# Sheet2.net
KiCad netlist of a schematic drawn in Altium Designer
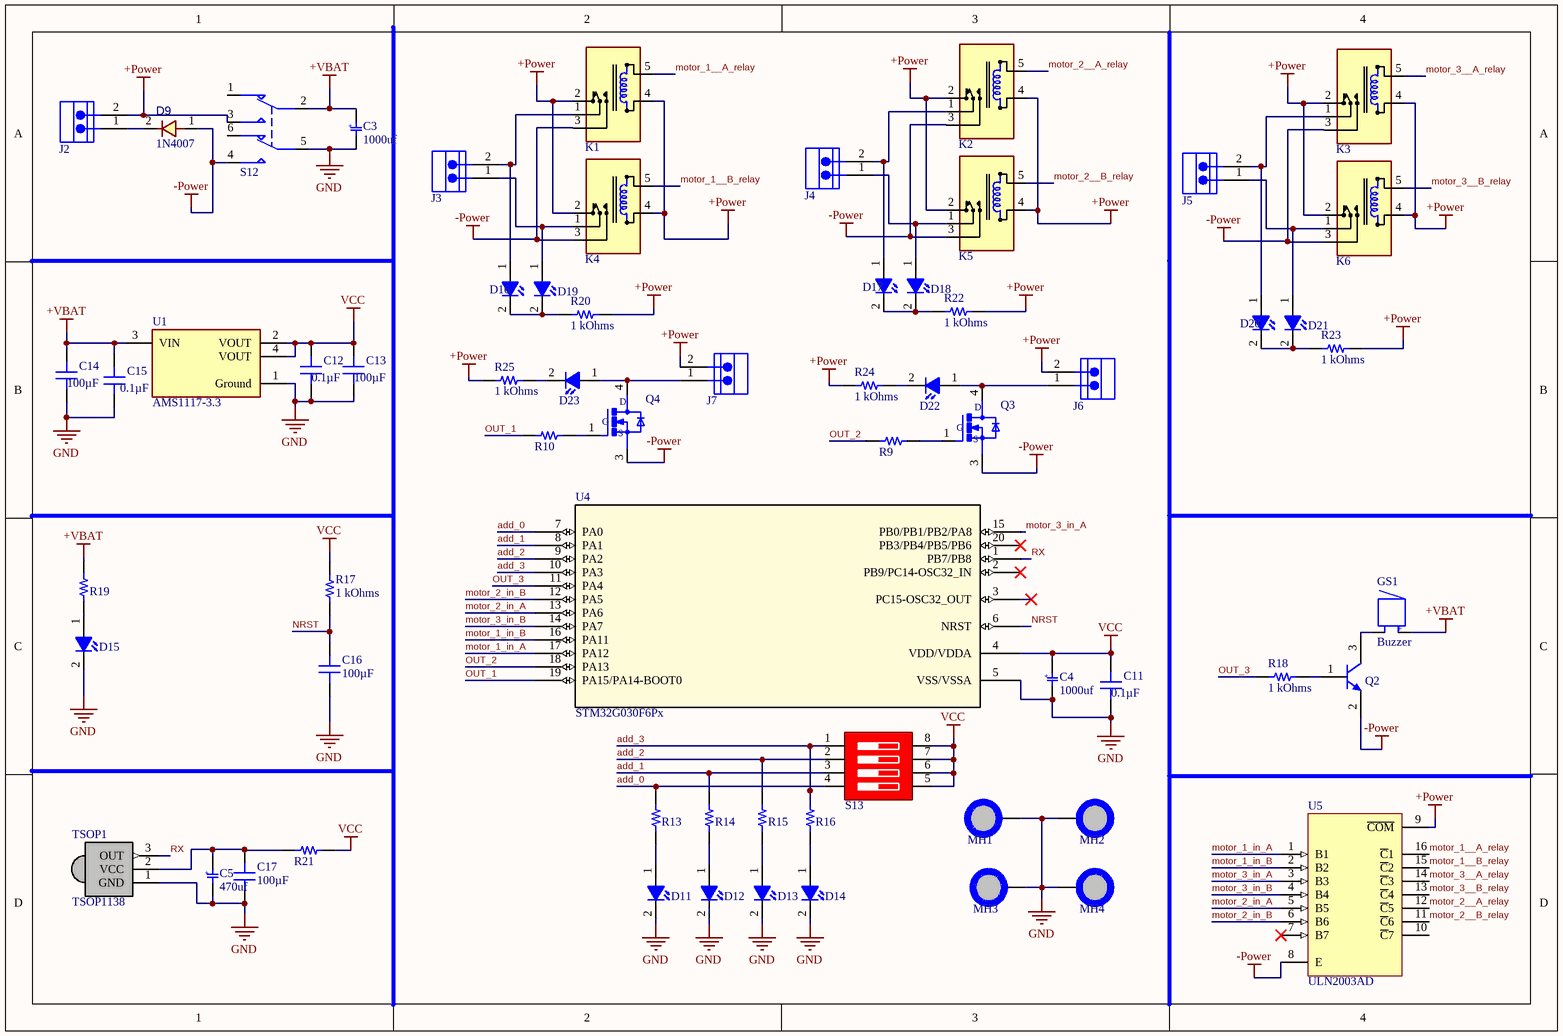
[diagram p0: Sheet2.SchDoc]

(export (version "E")
  (design (tool "Eeschema 10.0.6"))
  (components
    (comp (ref "C3")
      (value "1000uf")
      (footprint "Cap_3_(3.5mm)")
      (description "Capacitor Electrical THD")
      (libsource (lib "Schlib1") (part "Capacitor Electrical THD"))
    )
    (comp (ref "C4")
      (value "1000uf")
      (footprint "Cap_3_(3.5mm)")
      (description "Capacitor Electrical THD")
      (libsource (lib "Schlib1") (part "Capacitor Electrical THD"))
    )
    (comp (ref "C5")
      (value "470uf")
      (footprint "Cap_3_(3.5mm)")
      (description "Capacitor Electrical THD")
      (libsource (lib "Schlib1") (part "Capacitor Electrical THD"))
    )
    (comp (ref "C11")
      (value "0.1µF")
      (footprint "CAP 0805_2012")
      (description "CAP CER 0805 10% X8R 50V 100NF")
      (fields (field (name "PART NUMBER") "AC0805KKX8R9BB104") (field (name "MANUFACTURER") "Yageo"))
      (libsource (lib "Database_Libs1") (part "Capacitor"))
    )
    (comp (ref "C12")
      (value "0.1µF")
      (footprint "CAP 0805_2012")
      (description "CAP CER 0805 10% X8R 50V 100NF")
      (fields (field (name "PART NUMBER") "AC0805KKX8R9BB104") (field (name "MANUFACTURER") "Yageo"))
      (libsource (lib "Database_Libs1") (part "Capacitor"))
    )
    (comp (ref "C13")
      (value "100µF")
      (footprint "CAP 0805_2012")
      (description "CAP CER 100UF 6.3V X5R 0805")
      (fields
        (field (name "PART NUMBER") "GRM21BR60J107ME15L")
        (field (name "MANUFACTURER") "Murata Electronics")
      )
      (libsource (lib "Database_Libs1") (part "Capacitor"))
    )
    (comp (ref "C14")
      (value "100µF")
      (footprint "CAP 0805_2012")
      (description "CAP CER 100UF 6.3V X5R 0805")
      (fields
        (field (name "PART NUMBER") "GRM21BR60J107ME15L")
        (field (name "MANUFACTURER") "Murata Electronics")
      )
      (libsource (lib "Database_Libs1") (part "Capacitor"))
    )
    (comp (ref "C15")
      (value "0.1µF")
      (footprint "CAP 0805_2012")
      (description "CAP CER 0805 10% X8R 50V 100NF")
      (fields (field (name "PART NUMBER") "AC0805KKX8R9BB104") (field (name "MANUFACTURER") "Yageo"))
      (libsource (lib "Database_Libs1") (part "Capacitor"))
    )
    (comp (ref "C16")
      (value "100µF")
      (footprint "CAP 0805_2012")
      (description "CAP CER 100UF 6.3V X5R 0805")
      (fields
        (field (name "PART NUMBER") "GRM21BR60J107ME15L")
        (field (name "MANUFACTURER") "Murata Electronics")
      )
      (libsource (lib "Database_Libs1") (part "Capacitor"))
    )
    (comp (ref "C17")
      (value "100µF")
      (footprint "CAP 0805_2012")
      (description "CAP CER 100UF 6.3V X5R 0805")
      (fields
        (field (name "PART NUMBER") "GRM21BR60J107ME15L")
        (field (name "MANUFACTURER") "Murata Electronics")
      )
      (libsource (lib "Database_Libs1") (part "Capacitor"))
    )
    (comp (ref "D9")
      (value "1N4007")
      (footprint "D_SMA")
      (description "DIODE, GENERAL PURPOSE, 1000V/1A")
      (fields (field (name "Comment") "1N4007 SMD M7"))
      (libsource (lib "Schlib1") (part "1N4007 SMD M7"))
    )
    (comp (ref "D11")
      (value "LED THD 3mm")
      (footprint "LED THD 3mm (White)")
      (libsource (lib "Schlib1") (part "LED THD 3mm"))
    )
    (comp (ref "D12")
      (value "LED THD 3mm")
      (footprint "LED THD 3mm (White)")
      (libsource (lib "Schlib1") (part "LED THD 3mm"))
    )
    (comp (ref "D13")
      (value "LED THD 3mm")
      (footprint "LED THD 3mm (White)")
      (libsource (lib "Schlib1") (part "LED THD 3mm"))
    )
    (comp (ref "D14")
      (value "LED THD 3mm")
      (footprint "LED THD 3mm (White)")
      (libsource (lib "Schlib1") (part "LED THD 3mm"))
    )
    (comp (ref "D15")
      (value "LED THD 3mm")
      (footprint "LED THD 3mm (White)")
      (libsource (lib "Schlib1") (part "LED THD 3mm"))
    )
    (comp (ref "D16")
      (value "LED THD 3mm")
      (footprint "LED THD 3mm (White)")
      (libsource (lib "Schlib1") (part "LED THD 3mm"))
    )
    (comp (ref "D17")
      (value "LED THD 3mm")
      (footprint "LED THD 3mm (White)")
      (libsource (lib "Schlib1") (part "LED THD 3mm"))
    )
    (comp (ref "D18")
      (value "LED THD 3mm")
      (footprint "LED THD 3mm (White)")
      (libsource (lib "Schlib1") (part "LED THD 3mm"))
    )
    (comp (ref "D19")
      (value "LED THD 3mm")
      (footprint "LED THD 3mm (White)")
      (libsource (lib "Schlib1") (part "LED THD 3mm"))
    )
    (comp (ref "D20")
      (value "LED THD 3mm")
      (footprint "LED THD 3mm (White)")
      (libsource (lib "Schlib1") (part "LED THD 3mm"))
    )
    (comp (ref "D21")
      (value "LED THD 3mm")
      (footprint "LED THD 3mm (White)")
      (libsource (lib "Schlib1") (part "LED THD 3mm"))
    )
    (comp (ref "D22")
      (value "LED THD 3mm")
      (footprint "LED THD 3mm (White)")
      (libsource (lib "Schlib1") (part "LED THD 3mm"))
    )
    (comp (ref "D23")
      (value "LED THD 3mm")
      (footprint "LED THD 3mm (White)")
      (libsource (lib "Schlib1") (part "LED THD 3mm"))
    )
    (comp (ref "GS1")
      (value "Buzzer")
      (footprint "BZ_SJ")
      (description "Magnetic Transducer Buzzer")
      (fields (field (name "DESIGNER") "Eng. Saeid Jorablo") (field (name "PUBLISHER") "SJ Unlimited"))
      (libsource (lib "Schlib1") (part "Buzzer"))
    )
    (comp (ref "J2")
      (value "Socket Blue 2")
      (footprint "Socket Blue 2")
      (libsource (lib "Schlib1") (part "Socket Blue 2"))
    )
    (comp (ref "J3")
      (value "Socket Blue 2")
      (footprint "Socket Blue 2")
      (libsource (lib "Schlib1") (part "Socket Blue 2"))
    )
    (comp (ref "J4")
      (value "Socket Blue 2")
      (footprint "Socket Blue 2")
      (libsource (lib "Schlib1") (part "Socket Blue 2"))
    )
    (comp (ref "J5")
      (value "Socket Blue 2")
      (footprint "Socket Blue 2")
      (libsource (lib "Schlib1") (part "Socket Blue 2"))
    )
    (comp (ref "J6")
      (value "Socket Blue 2")
      (footprint "Socket Blue 2")
      (libsource (lib "Schlib1") (part "Socket Blue 2"))
    )
    (comp (ref "J7")
      (value "Socket Blue 2")
      (footprint "Socket Blue 2")
      (libsource (lib "Schlib1") (part "Socket Blue 2"))
    )
    (comp (ref "K1")
      (value "RELAY SPST 5 Pin Millon")
      (footprint "REL_SPDT_5_2216")
      (description "Relay")
      (libsource (lib "Schlib1") (part "RELAY SPST 5 Pin Millon"))
    )
    (comp (ref "K2")
      (value "RELAY SPST 5 Pin Millon")
      (footprint "REL_SPDT_5_2216")
      (description "Relay")
      (libsource (lib "Schlib1") (part "RELAY SPST 5 Pin Millon"))
    )
    (comp (ref "K3")
      (value "RELAY SPST 5 Pin Millon")
      (footprint "REL_SPDT_5_2216")
      (description "Relay")
      (libsource (lib "Schlib1") (part "RELAY SPST 5 Pin Millon"))
    )
    (comp (ref "K4")
      (value "RELAY SPST 5 Pin Millon")
      (footprint "REL_SPDT_5_2216")
      (description "Relay")
      (libsource (lib "Schlib1") (part "RELAY SPST 5 Pin Millon"))
    )
    (comp (ref "K5")
      (value "RELAY SPST 5 Pin Millon")
      (footprint "REL_SPDT_5_2216")
      (description "Relay")
      (libsource (lib "Schlib1") (part "RELAY SPST 5 Pin Millon"))
    )
    (comp (ref "K6")
      (value "RELAY SPST 5 Pin Millon")
      (footprint "REL_SPDT_5_2216")
      (description "Relay")
      (libsource (lib "Schlib1") (part "RELAY SPST 5 Pin Millon"))
    )
    (comp (ref "MH1")
      (value "MH_7.4mmC_3.2mmD")
      (footprint "MH_7.4mmC_3.2mmD")
      (description "MH_7.4MM Diameter,3.2mm Drill")
      (libsource (lib "Schlib1") (part "MH_7.4mmC_3.2mmD"))
    )
    (comp (ref "MH2")
      (value "MH_7.4mmC_3.2mmD")
      (footprint "MH_7.4mmC_3.2mmD")
      (description "MH_7.4MM Diameter,3.2mm Drill")
      (libsource (lib "Schlib1") (part "MH_7.4mmC_3.2mmD"))
    )
    (comp (ref "MH3")
      (value "MH_7.4mmC_3.2mmD")
      (footprint "MH_7.4mmC_3.2mmD")
      (description "MH_7.4MM Diameter,3.2mm Drill")
      (libsource (lib "Schlib1") (part "MH_7.4mmC_3.2mmD"))
    )
    (comp (ref "MH4")
      (value "MH_7.4mmC_3.2mmD")
      (footprint "MH_7.4mmC_3.2mmD")
      (description "MH_7.4MM Diameter,3.2mm Drill")
      (libsource (lib "Schlib1") (part "MH_7.4mmC_3.2mmD"))
    )
    (comp (ref "Q2")
      (value "MMBT2222A-7-F")
      (footprint "DIODES SOT-23-3")
      (description "TRANS NPN 40V 0.6A SMD SOT23-3")
      (fields (field (name "MANUFACTURER") "Diodes Incorporated"))
      (libsource (lib "Database_Libs1") (part "DIODES INC NPN SOT-23-3"))
    )
    (comp (ref "Q3")
      (value "PHD45N03LTA")
      (footprint "PcbLib1:TO228P1000X238-3N")
      (description "Bipolar Transistors - BJT")
      (fields (field (name "MF") "NXP USA"))
      (libsource (lib "Schlib1") (part "PHD45N03LTA"))
    )
    (comp (ref "Q4")
      (value "PHD45N03LTA")
      (footprint "PcbLib1:TO228P1000X238-3N")
      (description "Bipolar Transistors - BJT")
      (fields (field (name "MF") "NXP USA"))
      (libsource (lib "Schlib1") (part "PHD45N03LTA"))
    )
    (comp (ref "R9")
      (value "100 Ohms")
      (footprint "RES 0805_2012")
      (description "RES SMD 100 OHM 1% 0.4W 0805")
      (fields (field (name "PART NUMBER") "RCS0805100RFKEA") (field (name "MANUFACTURER") "Vishay Dale"))
      (libsource (lib "Database_Libs1") (part "Resistor"))
    )
    (comp (ref "R10")
      (value "100 Ohms")
      (footprint "RES 0805_2012")
      (description "RES SMD 100 OHM 1% 0.4W 0805")
      (fields (field (name "PART NUMBER") "RCS0805100RFKEA") (field (name "MANUFACTURER") "Vishay Dale"))
      (libsource (lib "Database_Libs1") (part "Resistor"))
    )
    (comp (ref "R13")
      (value "50 mOhms")
      (footprint "RES 0805_2012")
      (description "RES 0.05 OHM 1% 1/4W 0805")
      (fields (field (name "PART NUMBER") "CRM0805-FW-R050ELF") (field (name "MANUFACTURER") "Bourns Inc."))
      (libsource (lib "Database_Libs1") (part "Resistor"))
    )
    (comp (ref "R14")
      (value "50 mOhms")
      (footprint "RES 0805_2012")
      (description "RES 0.05 OHM 1% 1/4W 0805")
      (fields (field (name "PART NUMBER") "CRM0805-FW-R050ELF") (field (name "MANUFACTURER") "Bourns Inc."))
      (libsource (lib "Database_Libs1") (part "Resistor"))
    )
    (comp (ref "R15")
      (value "50 mOhms")
      (footprint "RES 0805_2012")
      (description "RES 0.05 OHM 1% 1/4W 0805")
      (fields (field (name "PART NUMBER") "CRM0805-FW-R050ELF") (field (name "MANUFACTURER") "Bourns Inc."))
      (libsource (lib "Database_Libs1") (part "Resistor"))
    )
    (comp (ref "R16")
      (value "50 mOhms")
      (footprint "RES 0805_2012")
      (description "RES 0.05 OHM 1% 1/4W 0805")
      (fields (field (name "PART NUMBER") "CRM0805-FW-R050ELF") (field (name "MANUFACTURER") "Bourns Inc."))
      (libsource (lib "Database_Libs1") (part "Resistor"))
    )
    (comp (ref "R17")
      (value "1 kOhms")
      (footprint "RES 0805_2012")
      (description "RES 1K OHM 1% 1/4W 0805")
      (fields
        (field (name "PART NUMBER") "RNCP0805FTD1K00")
        (field (name "MANUFACTURER") "Stackpole Electronics Inc")
      )
      (libsource (lib "Database_Libs1") (part "Resistor"))
    )
    (comp (ref "R18")
      (value "1 kOhms")
      (footprint "RES 0805_2012")
      (description "RES 1K OHM 1% 1/4W 0805")
      (fields
        (field (name "PART NUMBER") "RNCP0805FTD1K00")
        (field (name "MANUFACTURER") "Stackpole Electronics Inc")
      )
      (libsource (lib "Database_Libs1") (part "Resistor"))
    )
    (comp (ref "R19")
      (value "150 Ohms")
      (footprint "RES 0805_2012")
      (description "CRGP 0805 150R 1%")
      (fields
        (field (name "PART NUMBER") "CRGP0805F150R")
        (field (name "MANUFACTURER") "TE Connectivity Passive Product")
      )
      (libsource (lib "Database_Libs1") (part "Resistor"))
    )
    (comp (ref "R20")
      (value "1 kOhms")
      (footprint "RES 0805_2012")
      (description "RES 1K OHM 1% 1/4W 0805")
      (fields
        (field (name "PART NUMBER") "RNCP0805FTD1K00")
        (field (name "MANUFACTURER") "Stackpole Electronics Inc")
      )
      (libsource (lib "Database_Libs1") (part "Resistor"))
    )
    (comp (ref "R21")
      (value "100 Ohms")
      (footprint "RES 0805_2012")
      (description "CRGP 0805 100R 1%")
      (fields
        (field (name "PART NUMBER") "CRGP0805F100R")
        (field (name "MANUFACTURER") "TE Connectivity Passive Product")
      )
      (libsource (lib "Database_Libs1") (part "Resistor"))
    )
    (comp (ref "R22")
      (value "1 kOhms")
      (footprint "RES 0805_2012")
      (description "RES 1K OHM 1% 1/4W 0805")
      (fields
        (field (name "PART NUMBER") "RNCP0805FTD1K00")
        (field (name "MANUFACTURER") "Stackpole Electronics Inc")
      )
      (libsource (lib "Database_Libs1") (part "Resistor"))
    )
    (comp (ref "R23")
      (value "1 kOhms")
      (footprint "RES 0805_2012")
      (description "RES 1K OHM 1% 1/4W 0805")
      (fields
        (field (name "PART NUMBER") "RNCP0805FTD1K00")
        (field (name "MANUFACTURER") "Stackpole Electronics Inc")
      )
      (libsource (lib "Database_Libs1") (part "Resistor"))
    )
    (comp (ref "R24")
      (value "1 kOhms")
      (footprint "RES 0805_2012")
      (description "RES 1K OHM 1% 1/4W 0805")
      (fields
        (field (name "PART NUMBER") "RNCP0805FTD1K00")
        (field (name "MANUFACTURER") "Stackpole Electronics Inc")
      )
      (libsource (lib "Database_Libs1") (part "Resistor"))
    )
    (comp (ref "R25")
      (value "1 kOhms")
      (footprint "RES 0805_2012")
      (description "RES 1K OHM 1% 1/4W 0805")
      (fields
        (field (name "PART NUMBER") "RNCP0805FTD1K00")
        (field (name "MANUFACTURER") "Stackpole Electronics Inc")
      )
      (libsource (lib "Database_Libs1") (part "Resistor"))
    )
    (comp (ref "S12")
      (value "Double Switch")
      (footprint "SWPUST_DPDT_S2")
      (description "DPDT Switch")
      (libsource (lib "Schlib1") (part "SW DPDT"))
    )
    (comp (ref "S13")
      (value "DIP Switch 4")
      (footprint "dip switch 4  Blue THD")
      (description "4 BIT DIP Switch")
      (libsource (lib "Schlib1") (part "DIP Switch 4"))
    )
    (comp (ref "TSOP1")
      (value "TSOP1138")
      (footprint "TSOP11XX & 13XX")
      (description "IR Receiver Modules for Remote Control Systems")
      (libsource (lib "Schlib1") (part "TSOP1138"))
    )
    (comp (ref "U1")
      (value "AMS1117-3.3")
      (footprint "SOT223-4N")
      (description "LDO Voltage Regulators 1A, 3.3V")
      (fields
        (field (name "OCTOPART") "https://octopart.com/ams1117-3.3-advanced+monolithic+systems-25899300")
        (field (name "MANUFACTURER") "Advanced Monolithic Systems")
      )
      (libsource (lib "Schlib1") (part "CMP-209535-000001-1"))
    )
    (comp (ref "U4")
      (value "STM32G030F6Px")
      (footprint "TSSOP20")
      (fields
        (field (name "MANUFACTURER_PART_NUMBER") "stm32g0_tssop20_t1")
        (field (name "COPYRIGHT") "Copyright (C) 2018 Accelerated Designs. All rights reserved")
      )
      (libsource (lib "ST Microelectronics STM32 G0") (part "STM32G030F6Px"))
    )
    (comp (ref "U5")
      (value "ULN2003AD")
      (footprint "SOIC16")
      (description "Darlington Transistor Array")
      (fields (field (name "PUBLISHER") "Altium Limited"))
      (libsource (lib "Schlib1") (part "ULN2003AD"))
    )
  )
  (nets
    (net (code "1") (name "+Power") (class "Default")
      (node (ref "J2") (pin "2") (pinfunction "2_2") (pintype "passive"))
      (node (ref "J6") (pin "2") (pinfunction "2_2") (pintype "passive"))
      (node (ref "J7") (pin "2") (pinfunction "2_2") (pintype "passive"))
      (node (ref "K1") (pin "2") (pinfunction "NC_2") (pintype "passive"))
      (node (ref "K1") (pin "4") (pinfunction "T1_4") (pintype "passive"))
      (node (ref "K2") (pin "2") (pinfunction "NC_2") (pintype "passive"))
      (node (ref "K2") (pin "4") (pinfunction "T1_4") (pintype "passive"))
      (node (ref "K3") (pin "2") (pinfunction "NC_2") (pintype "passive"))
      (node (ref "K3") (pin "4") (pinfunction "T1_4") (pintype "passive"))
      (node (ref "K4") (pin "2") (pinfunction "NC_2") (pintype "passive"))
      (node (ref "K4") (pin "4") (pinfunction "T1_4") (pintype "passive"))
      (node (ref "K5") (pin "2") (pinfunction "NC_2") (pintype "passive"))
      (node (ref "K5") (pin "4") (pinfunction "T1_4") (pintype "passive"))
      (node (ref "K6") (pin "2") (pinfunction "NC_2") (pintype "passive"))
      (node (ref "K6") (pin "4") (pinfunction "T1_4") (pintype "passive"))
      (node (ref "R20") (pin "2") (pinfunction "2_2") (pintype "passive"))
      (node (ref "R22") (pin "2") (pinfunction "2_2") (pintype "passive"))
      (node (ref "R23") (pin "2") (pinfunction "2_2") (pintype "passive"))
      (node (ref "R24") (pin "1") (pinfunction "1_1") (pintype "passive"))
      (node (ref "R25") (pin "1") (pinfunction "1_1") (pintype "passive"))
      (node (ref "S12") (pin "3") (pinfunction "3_3") (pintype "passive"))
      (node (ref "U5") (pin "9") (pinfunction "~{COM}_9") (pintype "passive"))
    )
    (net (code "2") (name "+VBAT") (class "Default")
      (node (ref "C14") (pin "2") (pinfunction "2_2") (pintype "passive"))
      (node (ref "C15") (pin "2") (pinfunction "2_2") (pintype "passive"))
      (node (ref "C3") (pin "1") (pinfunction "1_1") (pintype "passive"))
      (node (ref "GS1") (pin "1") (pinfunction "+_1") (pintype "passive"))
      (node (ref "R19") (pin "2") (pinfunction "2_2") (pintype "passive"))
      (node (ref "S12") (pin "2") (pinfunction "2_2") (pintype "passive"))
      (node (ref "U1") (pin "3") (pinfunction "VIN_3") (pintype "power_in"))
    )
    (net (code "3") (name "-Power") (class "Default")
      (node (ref "D9") (pin "1") (pinfunction "1_1") (pintype "passive"))
      (node (ref "K1") (pin "3") (pinfunction "NO_3") (pintype "passive"))
      (node (ref "K2") (pin "3") (pinfunction "NO_3") (pintype "passive"))
      (node (ref "K3") (pin "3") (pinfunction "NO_3") (pintype "passive"))
      (node (ref "K4") (pin "3") (pinfunction "NO_3") (pintype "passive"))
      (node (ref "K5") (pin "3") (pinfunction "NO_3") (pintype "passive"))
      (node (ref "K6") (pin "3") (pinfunction "NO_3") (pintype "passive"))
      (node (ref "Q2") (pin "2") (pinfunction "E_2") (pintype "passive"))
      (node (ref "Q3") (pin "3") (pinfunction "S_3") (pintype "passive"))
      (node (ref "Q4") (pin "3") (pinfunction "S_3") (pintype "passive"))
      (node (ref "S12") (pin "4") (pinfunction "4_4") (pintype "passive"))
      (node (ref "U5") (pin "8") (pinfunction "E_8") (pintype "power_in"))
    )
    (net (code "4") (name "/NRST") (class "Default")
      (node (ref "C16") (pin "2") (pinfunction "2_2") (pintype "passive"))
      (node (ref "R17") (pin "2") (pinfunction "2_2") (pintype "passive"))
      (node (ref "U4") (pin "6") (pinfunction "NRST_6") (pintype "bidirectional"))
    )
    (net (code "5") (name "/OUT_1") (class "Default")
      (node (ref "R10") (pin "1") (pinfunction "1_1") (pintype "passive"))
      (node (ref "U4") (pin "19") (pinfunction "PA15/PA14-BOOT0_19") (pintype "bidirectional"))
    )
    (net (code "6") (name "/OUT_2") (class "Default")
      (node (ref "R9") (pin "1") (pinfunction "1_1") (pintype "passive"))
      (node (ref "U4") (pin "18") (pinfunction "PA13_18") (pintype "bidirectional"))
    )
    (net (code "7") (name "/OUT_3") (class "Default")
      (node (ref "R18") (pin "1") (pinfunction "1_1") (pintype "passive"))
      (node (ref "U4") (pin "11") (pinfunction "PA4_11") (pintype "bidirectional"))
    )
    (net (code "8") (name "/RX") (class "Default")
      (node (ref "TSOP1") (pin "3") (pinfunction "OUT_3") (pintype "output"))
      (node (ref "U4") (pin "1") (pinfunction "PB7/PB8_1") (pintype "bidirectional"))
    )
    (net (code "9") (name "/add_0") (class "Default")
      (node (ref "R13") (pin "2") (pinfunction "2_2") (pintype "passive"))
      (node (ref "S13") (pin "4") (pinfunction "4_4") (pintype "passive"))
      (node (ref "U4") (pin "7") (pinfunction "PA0_7") (pintype "bidirectional"))
    )
    (net (code "10") (name "/add_1") (class "Default")
      (node (ref "R14") (pin "2") (pinfunction "2_2") (pintype "passive"))
      (node (ref "S13") (pin "3") (pinfunction "3_3") (pintype "passive"))
      (node (ref "U4") (pin "8") (pinfunction "PA1_8") (pintype "bidirectional"))
    )
    (net (code "11") (name "/add_2") (class "Default")
      (node (ref "R15") (pin "2") (pinfunction "2_2") (pintype "passive"))
      (node (ref "S13") (pin "2") (pinfunction "2_2") (pintype "passive"))
      (node (ref "U4") (pin "9") (pinfunction "PA2_9") (pintype "bidirectional"))
    )
    (net (code "12") (name "/add_3") (class "Default")
      (node (ref "R16") (pin "2") (pinfunction "2_2") (pintype "passive"))
      (node (ref "S13") (pin "1") (pinfunction "1_1") (pintype "passive"))
      (node (ref "U4") (pin "10") (pinfunction "PA3_10") (pintype "bidirectional"))
    )
    (net (code "13") (name "/motor_1__A_relay") (class "Default")
      (node (ref "K1") (pin "5") (pinfunction "T2_5") (pintype "passive"))
      (node (ref "U5") (pin "16") (pinfunction "~{C}1_16") (pintype "open_collector"))
    )
    (net (code "14") (name "/motor_1__B_relay") (class "Default")
      (node (ref "K4") (pin "5") (pinfunction "T2_5") (pintype "passive"))
      (node (ref "U5") (pin "15") (pinfunction "~{C}2_15") (pintype "open_collector"))
    )
    (net (code "15") (name "/motor_1_in_A") (class "Default")
      (node (ref "U4") (pin "17") (pinfunction "PA12_17") (pintype "bidirectional"))
      (node (ref "U5") (pin "1") (pinfunction "B1_1") (pintype "input"))
    )
    (net (code "16") (name "/motor_1_in_B") (class "Default")
      (node (ref "U4") (pin "16") (pinfunction "PA11_16") (pintype "bidirectional"))
      (node (ref "U5") (pin "2") (pinfunction "B2_2") (pintype "input"))
    )
    (net (code "17") (name "/motor_2__A_relay") (class "Default")
      (node (ref "K2") (pin "5") (pinfunction "T2_5") (pintype "passive"))
      (node (ref "U5") (pin "12") (pinfunction "~{C}5_12") (pintype "open_collector"))
    )
    (net (code "18") (name "/motor_2__B_relay") (class "Default")
      (node (ref "K5") (pin "5") (pinfunction "T2_5") (pintype "passive"))
      (node (ref "U5") (pin "11") (pinfunction "~{C}6_11") (pintype "open_collector"))
    )
    (net (code "19") (name "/motor_2_in_A") (class "Default")
      (node (ref "U4") (pin "13") (pinfunction "PA6_13") (pintype "bidirectional"))
      (node (ref "U5") (pin "5") (pinfunction "B5_5") (pintype "input"))
    )
    (net (code "20") (name "/motor_2_in_B") (class "Default")
      (node (ref "U4") (pin "12") (pinfunction "PA5_12") (pintype "bidirectional"))
      (node (ref "U5") (pin "6") (pinfunction "B6_6") (pintype "input"))
    )
    (net (code "21") (name "/motor_3__A_relay") (class "Default")
      (node (ref "K3") (pin "5") (pinfunction "T2_5") (pintype "passive"))
      (node (ref "U5") (pin "14") (pinfunction "~{C}3_14") (pintype "open_collector"))
    )
    (net (code "22") (name "/motor_3__B_relay") (class "Default")
      (node (ref "K6") (pin "5") (pinfunction "T2_5") (pintype "passive"))
      (node (ref "U5") (pin "13") (pinfunction "~{C}4_13") (pintype "open_collector"))
    )
    (net (code "23") (name "/motor_3_in_A") (class "Default")
      (node (ref "U4") (pin "15") (pinfunction "PB0/PB1/PB2/PA8_15") (pintype "bidirectional"))
      (node (ref "U5") (pin "3") (pinfunction "B3_3") (pintype "input"))
    )
    (net (code "24") (name "/motor_3_in_B") (class "Default")
      (node (ref "U4") (pin "14") (pinfunction "PA7_14") (pintype "bidirectional"))
      (node (ref "U5") (pin "4") (pinfunction "B4_4") (pintype "input"))
    )
    (net (code "25") (name "GND") (class "Default")
      (node (ref "C11") (pin "1") (pinfunction "1_1") (pintype "passive"))
      (node (ref "C12") (pin "1") (pinfunction "1_1") (pintype "passive"))
      (node (ref "C13") (pin "1") (pinfunction "1_1") (pintype "passive"))
      (node (ref "C14") (pin "1") (pinfunction "1_1") (pintype "passive"))
      (node (ref "C15") (pin "1") (pinfunction "1_1") (pintype "passive"))
      (node (ref "C16") (pin "1") (pinfunction "1_1") (pintype "passive"))
      (node (ref "C17") (pin "1") (pinfunction "1_1") (pintype "passive"))
      (node (ref "C3") (pin "2") (pinfunction "2_2") (pintype "passive"))
      (node (ref "C4") (pin "2") (pinfunction "2_2") (pintype "passive"))
      (node (ref "C5") (pin "2") (pinfunction "2_2") (pintype "passive"))
      (node (ref "D11") (pin "2") (pinfunction "CATHODE_2") (pintype "passive"))
      (node (ref "D12") (pin "2") (pinfunction "CATHODE_2") (pintype "passive"))
      (node (ref "D13") (pin "2") (pinfunction "CATHODE_2") (pintype "passive"))
      (node (ref "D14") (pin "2") (pinfunction "CATHODE_2") (pintype "passive"))
      (node (ref "D15") (pin "2") (pinfunction "CATHODE_2") (pintype "passive"))
      (node (ref "MH1") (pin "0") (pinfunction "0_0") (pintype "passive"))
      (node (ref "MH2") (pin "0") (pinfunction "0_0") (pintype "passive"))
      (node (ref "MH3") (pin "0") (pinfunction "0_0") (pintype "passive"))
      (node (ref "MH4") (pin "0") (pinfunction "0_0") (pintype "passive"))
      (node (ref "S12") (pin "5") (pinfunction "5_5") (pintype "passive"))
      (node (ref "TSOP1") (pin "1") (pinfunction "GND_1") (pintype "power_in"))
      (node (ref "U1") (pin "1") (pinfunction "Ground_1") (pintype "power_in"))
      (node (ref "U4") (pin "5") (pinfunction "VSS/VSSA_5") (pintype "power_in"))
    )
    (net (code "26") (name "Net-(D9-Pad2)") (class "Default")
      (node (ref "D9") (pin "2") (pinfunction "2_2") (pintype "passive"))
      (node (ref "J2") (pin "1") (pinfunction "1_1") (pintype "passive"))
    )
    (net (code "27") (name "Net-(D11-ANODE)") (class "Default")
      (node (ref "D11") (pin "1") (pinfunction "ANODE_1") (pintype "passive"))
      (node (ref "R13") (pin "1") (pinfunction "1_1") (pintype "passive"))
    )
    (net (code "28") (name "Net-(D12-ANODE)") (class "Default")
      (node (ref "D12") (pin "1") (pinfunction "ANODE_1") (pintype "passive"))
      (node (ref "R14") (pin "1") (pinfunction "1_1") (pintype "passive"))
    )
    (net (code "29") (name "Net-(D13-ANODE)") (class "Default")
      (node (ref "D13") (pin "1") (pinfunction "ANODE_1") (pintype "passive"))
      (node (ref "R15") (pin "1") (pinfunction "1_1") (pintype "passive"))
    )
    (net (code "30") (name "Net-(D14-ANODE)") (class "Default")
      (node (ref "D14") (pin "1") (pinfunction "ANODE_1") (pintype "passive"))
      (node (ref "R16") (pin "1") (pinfunction "1_1") (pintype "passive"))
    )
    (net (code "31") (name "Net-(D15-ANODE)") (class "Default")
      (node (ref "D15") (pin "1") (pinfunction "ANODE_1") (pintype "passive"))
      (node (ref "R19") (pin "1") (pinfunction "1_1") (pintype "passive"))
    )
    (net (code "32") (name "Net-(D16-ANODE)") (class "Default")
      (node (ref "D16") (pin "1") (pinfunction "ANODE_1") (pintype "passive"))
      (node (ref "J3") (pin "2") (pinfunction "2_2") (pintype "passive"))
      (node (ref "K1") (pin "1") (pinfunction "COM_1") (pintype "passive"))
    )
    (net (code "33") (name "Net-(D16-CATHODE)") (class "Default")
      (node (ref "D16") (pin "2") (pinfunction "CATHODE_2") (pintype "passive"))
      (node (ref "D19") (pin "2") (pinfunction "CATHODE_2") (pintype "passive"))
      (node (ref "R20") (pin "1") (pinfunction "1_1") (pintype "passive"))
    )
    (net (code "34") (name "Net-(D17-ANODE)") (class "Default")
      (node (ref "D17") (pin "1") (pinfunction "ANODE_1") (pintype "passive"))
      (node (ref "J4") (pin "2") (pinfunction "2_2") (pintype "passive"))
      (node (ref "K2") (pin "1") (pinfunction "COM_1") (pintype "passive"))
    )
    (net (code "35") (name "Net-(D17-CATHODE)") (class "Default")
      (node (ref "D17") (pin "2") (pinfunction "CATHODE_2") (pintype "passive"))
      (node (ref "D18") (pin "2") (pinfunction "CATHODE_2") (pintype "passive"))
      (node (ref "R22") (pin "1") (pinfunction "1_1") (pintype "passive"))
    )
    (net (code "36") (name "Net-(D18-ANODE)") (class "Default")
      (node (ref "D18") (pin "1") (pinfunction "ANODE_1") (pintype "passive"))
      (node (ref "J4") (pin "1") (pinfunction "1_1") (pintype "passive"))
      (node (ref "K5") (pin "1") (pinfunction "COM_1") (pintype "passive"))
    )
    (net (code "37") (name "Net-(D19-ANODE)") (class "Default")
      (node (ref "D19") (pin "1") (pinfunction "ANODE_1") (pintype "passive"))
      (node (ref "J3") (pin "1") (pinfunction "1_1") (pintype "passive"))
      (node (ref "K4") (pin "1") (pinfunction "COM_1") (pintype "passive"))
    )
    (net (code "38") (name "Net-(D20-ANODE)") (class "Default")
      (node (ref "D20") (pin "1") (pinfunction "ANODE_1") (pintype "passive"))
      (node (ref "J5") (pin "2") (pinfunction "2_2") (pintype "passive"))
      (node (ref "K3") (pin "1") (pinfunction "COM_1") (pintype "passive"))
    )
    (net (code "39") (name "Net-(D20-CATHODE)") (class "Default")
      (node (ref "D20") (pin "2") (pinfunction "CATHODE_2") (pintype "passive"))
      (node (ref "D21") (pin "2") (pinfunction "CATHODE_2") (pintype "passive"))
      (node (ref "R23") (pin "1") (pinfunction "1_1") (pintype "passive"))
    )
    (net (code "40") (name "Net-(D21-ANODE)") (class "Default")
      (node (ref "D21") (pin "1") (pinfunction "ANODE_1") (pintype "passive"))
      (node (ref "J5") (pin "1") (pinfunction "1_1") (pintype "passive"))
      (node (ref "K6") (pin "1") (pinfunction "COM_1") (pintype "passive"))
    )
    (net (code "41") (name "Net-(D22-ANODE)") (class "Default")
      (node (ref "D22") (pin "1") (pinfunction "ANODE_1") (pintype "passive"))
      (node (ref "J6") (pin "1") (pinfunction "1_1") (pintype "passive"))
      (node (ref "Q3") (pin "4") (pinfunction "D_4") (pintype "passive"))
    )
    (net (code "42") (name "Net-(D22-CATHODE)") (class "Default")
      (node (ref "D22") (pin "2") (pinfunction "CATHODE_2") (pintype "passive"))
      (node (ref "R24") (pin "2") (pinfunction "2_2") (pintype "passive"))
    )
    (net (code "43") (name "Net-(D23-ANODE)") (class "Default")
      (node (ref "D23") (pin "1") (pinfunction "ANODE_1") (pintype "passive"))
      (node (ref "J7") (pin "1") (pinfunction "1_1") (pintype "passive"))
      (node (ref "Q4") (pin "4") (pinfunction "D_4") (pintype "passive"))
    )
    (net (code "44") (name "Net-(D23-CATHODE)") (class "Default")
      (node (ref "D23") (pin "2") (pinfunction "CATHODE_2") (pintype "passive"))
      (node (ref "R25") (pin "2") (pinfunction "2_2") (pintype "passive"))
    )
    (net (code "45") (name "Net-(GS1--)") (class "Default")
      (node (ref "GS1") (pin "2") (pinfunction "-_2") (pintype "passive"))
      (node (ref "Q2") (pin "3") (pinfunction "C_3") (pintype "passive"))
    )
    (net (code "46") (name "Net-(Q2-B)") (class "Default")
      (node (ref "Q2") (pin "1") (pinfunction "B_1") (pintype "passive"))
      (node (ref "R18") (pin "2") (pinfunction "2_2") (pintype "passive"))
    )
    (net (code "47") (name "Net-(Q3-G)") (class "Default")
      (node (ref "Q3") (pin "1") (pinfunction "G_1") (pintype "passive"))
      (node (ref "R9") (pin "2") (pinfunction "2_2") (pintype "passive"))
    )
    (net (code "48") (name "Net-(Q4-G)") (class "Default")
      (node (ref "Q4") (pin "1") (pinfunction "G_1") (pintype "passive"))
      (node (ref "R10") (pin "2") (pinfunction "2_2") (pintype "passive"))
    )
    (net (code "49") (name "Net-(TSOP1-VCC)") (class "Default")
      (node (ref "C17") (pin "2") (pinfunction "2_2") (pintype "passive"))
      (node (ref "C5") (pin "1") (pinfunction "1_1") (pintype "passive"))
      (node (ref "R21") (pin "1") (pinfunction "1_1") (pintype "passive"))
      (node (ref "TSOP1") (pin "2") (pinfunction "VCC_2") (pintype "power_in"))
    )
    (net (code "50") (name "VCC") (class "Default")
      (node (ref "C11") (pin "2") (pinfunction "2_2") (pintype "passive"))
      (node (ref "C12") (pin "2") (pinfunction "2_2") (pintype "passive"))
      (node (ref "C13") (pin "2") (pinfunction "2_2") (pintype "passive"))
      (node (ref "C4") (pin "1") (pinfunction "1_1") (pintype "passive"))
      (node (ref "R17") (pin "1") (pinfunction "1_1") (pintype "passive"))
      (node (ref "R21") (pin "2") (pinfunction "2_2") (pintype "passive"))
      (node (ref "S13") (pin "5") (pinfunction "5_5") (pintype "passive"))
      (node (ref "S13") (pin "6") (pinfunction "6_6") (pintype "passive"))
      (node (ref "S13") (pin "7") (pinfunction "7_7") (pintype "passive"))
      (node (ref "S13") (pin "8") (pinfunction "8_8") (pintype "passive"))
      (node (ref "U1") (pin "2") (pinfunction "VOUT_2") (pintype "passive"))
      (node (ref "U1") (pin "4") (pinfunction "VOUT_4") (pintype "passive"))
      (node (ref "U4") (pin "4") (pinfunction "VDD/VDDA_4") (pintype "power_in"))
    )
    (net (code "51") (name "unconnected-(S12-Pad1)") (class "Default")
      (node (ref "S12") (pin "1") (pinfunction "1_1") (pintype "passive"))
    )
    (net (code "52") (name "unconnected-(S12-Pad6)") (class "Default")
      (node (ref "S12") (pin "6") (pinfunction "6_6") (pintype "passive"))
    )
    (net (code "53") (name "unconnected-(U4-PB3{slash}PB4{slash}PB5{slash}PB6-Pad20)") (class "Default")
      (node (ref "U4") (pin "20") (pinfunction "PB3/PB4/PB5/PB6_20") (pintype "bidirectional+no_connect"))
    )
    (net (code "54") (name "unconnected-(U4-PB9{slash}PC14-OSC32_IN-Pad2)") (class "Default")
      (node (ref "U4") (pin "2") (pinfunction "PB9/PC14-OSC32_IN_2") (pintype "bidirectional+no_connect"))
    )
    (net (code "55") (name "unconnected-(U4-PC15-OSC32_OUT-Pad3)") (class "Default")
      (node (ref "U4") (pin "3") (pinfunction "PC15-OSC32_OUT_3") (pintype "bidirectional+no_connect"))
    )
    (net (code "56") (name "unconnected-(U5-B7-Pad7)") (class "Default")
      (node (ref "U5") (pin "7") (pinfunction "B7_7") (pintype "input+no_connect"))
    )
    (net (code "57") (name "unconnected-(U5-~{C}7-Pad10)") (class "Default")
      (node (ref "U5") (pin "10") (pinfunction "~{C}7_10") (pintype "open_collector"))
    )
  )
)
